# Power_Switch.net
KiCad netlist of a schematic drawn in Altium Designer
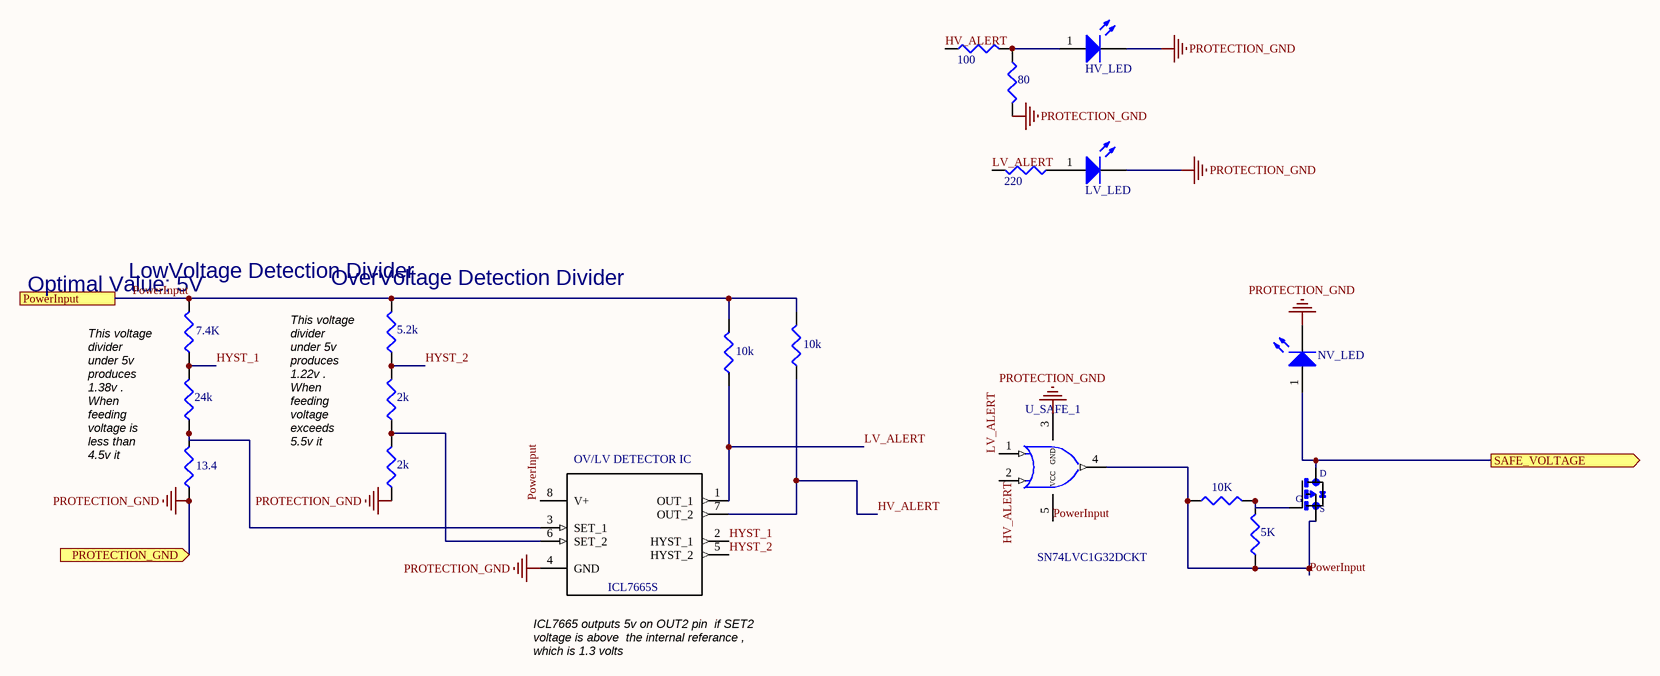
[diagram p0: Power_Switch.SchDoc]

(export (version "E")
  (design (tool "Eeschema 10.0.6"))
  (components
    (comp (ref "HV_LED")
      (value "L_green")
      (footprint "LED_0603")
      (libsource (lib "Led_edited") (part "L_green"))
    )
    (comp (ref "LV_LED")
      (value "L_green")
      (footprint "LED_0603")
      (libsource (lib "Led_edited") (part "L_green"))
    )
    (comp (ref "MOS_SAFE_1")
      (value "SI2323DS-T1-GE3")
      (footprint "*SOT23")
      (description "Single P-Channel 20 V 0.039 O 19 nC Surface Mount Power Mosfet - SOT-23")
      (fields (field (name "MF") "Vishay"))
      (libsource (lib "mosfetP_sot23") (part "PMOS"))
    )
    (comp (ref "NV_LED")
      (value "L_green")
      (footprint "LED_0603")
      (libsource (lib "Led_edited") (part "L_green"))
    )
    (comp (ref "OV/LV DETECTOR IC")
      (value "ICL7665S")
      (footprint "*SOIC127P600X175-8N")
      (description "CMOS Micropower Over/Under Voltage Detector")
      (fields (field (name "MF") "Renesas Electronics") (field (name "MP") "ICL7665SCBAZA-T"))
      (libsource (lib "ICL7665SCBAZA-T") (part "ICL7665SCBAZA-T"))
    )
    (comp (ref "RHV1")
      (value "5.2k")
      (footprint "1608(0603)")
      (description "Resistor")
      (fields (field (name "Comment") "Res3") (field (name "PUBLISHER") "Altium Limited"))
      (libsource (lib "Miscellaneous Devices") (part "Res3"))
    )
    (comp (ref "RHV2")
      (value "2k")
      (footprint "1608(0603)")
      (description "Resistor")
      (fields (field (name "Comment") "Res3") (field (name "PUBLISHER") "Altium Limited"))
      (libsource (lib "Miscellaneous Devices") (part "Res3"))
    )
    (comp (ref "RHV3")
      (value "2k")
      (footprint "1608(0603)")
      (description "Resistor")
      (fields (field (name "Comment") "Res3") (field (name "PUBLISHER") "Altium Limited"))
      (libsource (lib "Miscellaneous Devices") (part "Res3"))
    )
    (comp (ref "RHV_ALERT1")
      (value "100")
      (footprint "1608(0603)")
      (description "Resistor")
      (fields (field (name "Comment") "Res3") (field (name "PUBLISHER") "Altium Limited"))
      (libsource (lib "Miscellaneous Devices") (part "Res3"))
    )
    (comp (ref "RHV_ALERT2")
      (value "80")
      (footprint "1608(0603)")
      (description "Resistor")
      (fields (field (name "Comment") "Res3") (field (name "PUBLISHER") "Altium Limited"))
      (libsource (lib "Miscellaneous Devices") (part "Res3"))
    )
    (comp (ref "RICLOUT1")
      (value "10k")
      (footprint "1608(0603)")
      (description "Resistor")
      (fields (field (name "Comment") "Res3") (field (name "PUBLISHER") "Altium Limited"))
      (libsource (lib "Miscellaneous Devices") (part "Res3"))
    )
    (comp (ref "RICL_OUT2")
      (value "10k")
      (footprint "1608(0603)")
      (description "Resistor")
      (fields (field (name "Comment") "Res3") (field (name "PUBLISHER") "Altium Limited"))
      (libsource (lib "Miscellaneous Devices") (part "Res3"))
    )
    (comp (ref "RLV1")
      (value "7.4K")
      (footprint "1608(0603)")
      (description "Resistor")
      (fields (field (name "Comment") "Res3") (field (name "PUBLISHER") "Altium Limited"))
      (libsource (lib "Miscellaneous Devices") (part "Res3"))
    )
    (comp (ref "RLV2")
      (value "24k")
      (footprint "1608(0603)")
      (description "Resistor")
      (fields (field (name "Comment") "Res3") (field (name "PUBLISHER") "Altium Limited"))
      (libsource (lib "Miscellaneous Devices") (part "Res3"))
    )
    (comp (ref "RLV3")
      (value "13.4")
      (footprint "1608(0603)")
      (description "Resistor")
      (fields (field (name "Comment") "Res3") (field (name "PUBLISHER") "Altium Limited"))
      (libsource (lib "Miscellaneous Devices") (part "Res3"))
    )
    (comp (ref "RLV_ALERT1")
      (value "220")
      (footprint "1608(0603)")
      (description "Resistor")
      (fields (field (name "Comment") "Res3") (field (name "PUBLISHER") "Altium Limited"))
      (libsource (lib "Miscellaneous Devices") (part "Res3"))
    )
    (comp (ref "R_SAFE_10")
      (value "10K")
      (footprint "1608(0603)")
      (description "Resistor")
      (fields (field (name "Comment") "Res3") (field (name "PUBLISHER") "Altium Limited"))
      (libsource (lib "Miscellaneous Devices") (part "Res3"))
    )
    (comp (ref "R_SAFE_11")
      (value "5K")
      (footprint "1608(0603)")
      (description "Resistor")
      (fields (field (name "Comment") "Res3") (field (name "PUBLISHER") "Altium Limited"))
      (libsource (lib "Miscellaneous Devices") (part "Res3"))
    )
    (comp (ref "U_SAFE_1")
      (value "SN74LVC1G32DCKT")
      (footprint "*SOT65P210X110-5N")
      (description "Single 2-Input Positive-O Gate 5-SC70 -40 to 125")
      (fields (field (name "MF") "Texas Instruments"))
      (libsource (lib "SN74LVC1G32_OR_GATE") (part "SN74LVC1"))
    )
  )
  (nets
    (net (code "1") (name "/HV_ALERT") (class "Default")
      (node (ref "OV/LV DETECTOR IC") (pin "7") (pinfunction "OUT_2_7") (pintype "output"))
      (node (ref "RHV_ALERT1") (pin "1") (pinfunction "1_1") (pintype "passive"))
      (node (ref "RICL_OUT2") (pin "1") (pinfunction "1_1") (pintype "passive"))
      (node (ref "U_SAFE_1") (pin "2") (pinfunction "2_2") (pintype "input"))
    )
    (net (code "2") (name "/HYST_1") (class "Default")
      (node (ref "OV/LV DETECTOR IC") (pin "2") (pinfunction "HYST_1_2") (pintype "output"))
      (node (ref "RLV1") (pin "1") (pinfunction "1_1") (pintype "passive"))
      (node (ref "RLV2") (pin "2") (pinfunction "2_2") (pintype "passive"))
    )
    (net (code "3") (name "/HYST_2") (class "Default")
      (node (ref "OV/LV DETECTOR IC") (pin "5") (pinfunction "HYST_2_5") (pintype "output"))
      (node (ref "RHV1") (pin "1") (pinfunction "1_1") (pintype "passive"))
      (node (ref "RHV2") (pin "2") (pinfunction "2_2") (pintype "passive"))
    )
    (net (code "4") (name "/LV_ALERT") (class "Default")
      (node (ref "OV/LV DETECTOR IC") (pin "1") (pinfunction "OUT_1_1") (pintype "output"))
      (node (ref "RICLOUT1") (pin "1") (pinfunction "1_1") (pintype "passive"))
      (node (ref "RLV_ALERT1") (pin "2") (pinfunction "2_2") (pintype "passive"))
      (node (ref "U_SAFE_1") (pin "1") (pinfunction "A_1") (pintype "input"))
    )
    (net (code "5") (name "/PowerInput") (class "Default")
      (node (ref "MOS_SAFE_1") (pin "2") (pinfunction "S_2") (pintype "passive"))
      (node (ref "OV/LV DETECTOR IC") (pin "8") (pinfunction "V+_8") (pintype "power_in"))
      (node (ref "RHV1") (pin "2") (pinfunction "2_2") (pintype "passive"))
      (node (ref "RICLOUT1") (pin "2") (pinfunction "2_2") (pintype "passive"))
      (node (ref "RICL_OUT2") (pin "2") (pinfunction "2_2") (pintype "passive"))
      (node (ref "RLV1") (pin "2") (pinfunction "2_2") (pintype "passive"))
      (node (ref "R_SAFE_10") (pin "1") (pinfunction "1_1") (pintype "passive"))
      (node (ref "R_SAFE_11") (pin "1") (pinfunction "1_1") (pintype "passive"))
      (node (ref "U_SAFE_1") (pin "4") (pinfunction "Y_4") (pintype "output"))
      (node (ref "U_SAFE_1") (pin "5") (pinfunction "VCC_5") (pintype "power_in"))
    )
    (net (code "6") (name "/SAFE_VOLTAGE") (class "Default")
      (node (ref "MOS_SAFE_1") (pin "3") (pinfunction "D_3") (pintype "passive"))
      (node (ref "NV_LED") (pin "1") (pinfunction "V_1") (pintype "passive"))
    )
    (net (code "7") (name "Net-(HV_LED-V)") (class "Default")
      (node (ref "HV_LED") (pin "1") (pinfunction "V_1") (pintype "passive"))
      (node (ref "RHV_ALERT1") (pin "2") (pinfunction "2_2") (pintype "passive"))
      (node (ref "RHV_ALERT2") (pin "1") (pinfunction "1_1") (pintype "passive"))
    )
    (net (code "8") (name "Net-(LV_LED-V)") (class "Default")
      (node (ref "LV_LED") (pin "1") (pinfunction "V_1") (pintype "passive"))
      (node (ref "RLV_ALERT1") (pin "1") (pinfunction "1_1") (pintype "passive"))
    )
    (net (code "9") (name "Net-(MOS_SAFE_1-G)") (class "Default")
      (node (ref "MOS_SAFE_1") (pin "1") (pinfunction "G_1") (pintype "passive"))
      (node (ref "R_SAFE_10") (pin "2") (pinfunction "2_2") (pintype "passive"))
      (node (ref "R_SAFE_11") (pin "2") (pinfunction "2_2") (pintype "passive"))
    )
    (net (code "10") (name "Net-(OV/LV DETECTOR IC-SET_1)") (class "Default")
      (node (ref "OV/LV DETECTOR IC") (pin "3") (pinfunction "SET_1_3") (pintype "input"))
      (node (ref "RLV2") (pin "1") (pinfunction "1_1") (pintype "passive"))
      (node (ref "RLV3") (pin "2") (pinfunction "2_2") (pintype "passive"))
    )
    (net (code "11") (name "Net-(OV/LV DETECTOR IC-SET_2)") (class "Default")
      (node (ref "OV/LV DETECTOR IC") (pin "6") (pinfunction "SET_2_6") (pintype "input"))
      (node (ref "RHV2") (pin "1") (pinfunction "1_1") (pintype "passive"))
      (node (ref "RHV3") (pin "2") (pinfunction "2_2") (pintype "passive"))
    )
    (net (code "12") (name "PROTECTION_GND") (class "Default")
      (node (ref "HV_LED") (pin "2") (pinfunction "K_2") (pintype "passive"))
      (node (ref "LV_LED") (pin "2") (pinfunction "K_2") (pintype "passive"))
      (node (ref "NV_LED") (pin "2") (pinfunction "K_2") (pintype "passive"))
      (node (ref "OV/LV DETECTOR IC") (pin "4") (pinfunction "GND_4") (pintype "passive"))
      (node (ref "RHV3") (pin "1") (pinfunction "1_1") (pintype "passive"))
      (node (ref "RHV_ALERT2") (pin "2") (pinfunction "2_2") (pintype "passive"))
      (node (ref "RLV3") (pin "1") (pinfunction "1_1") (pintype "passive"))
      (node (ref "U_SAFE_1") (pin "3") (pinfunction "GND_3") (pintype "passive"))
    )
  )
)
